# SCH_Mini-Converter_2024-05-02.net
KiCad netlist of a schematic drawn in EasyEDA
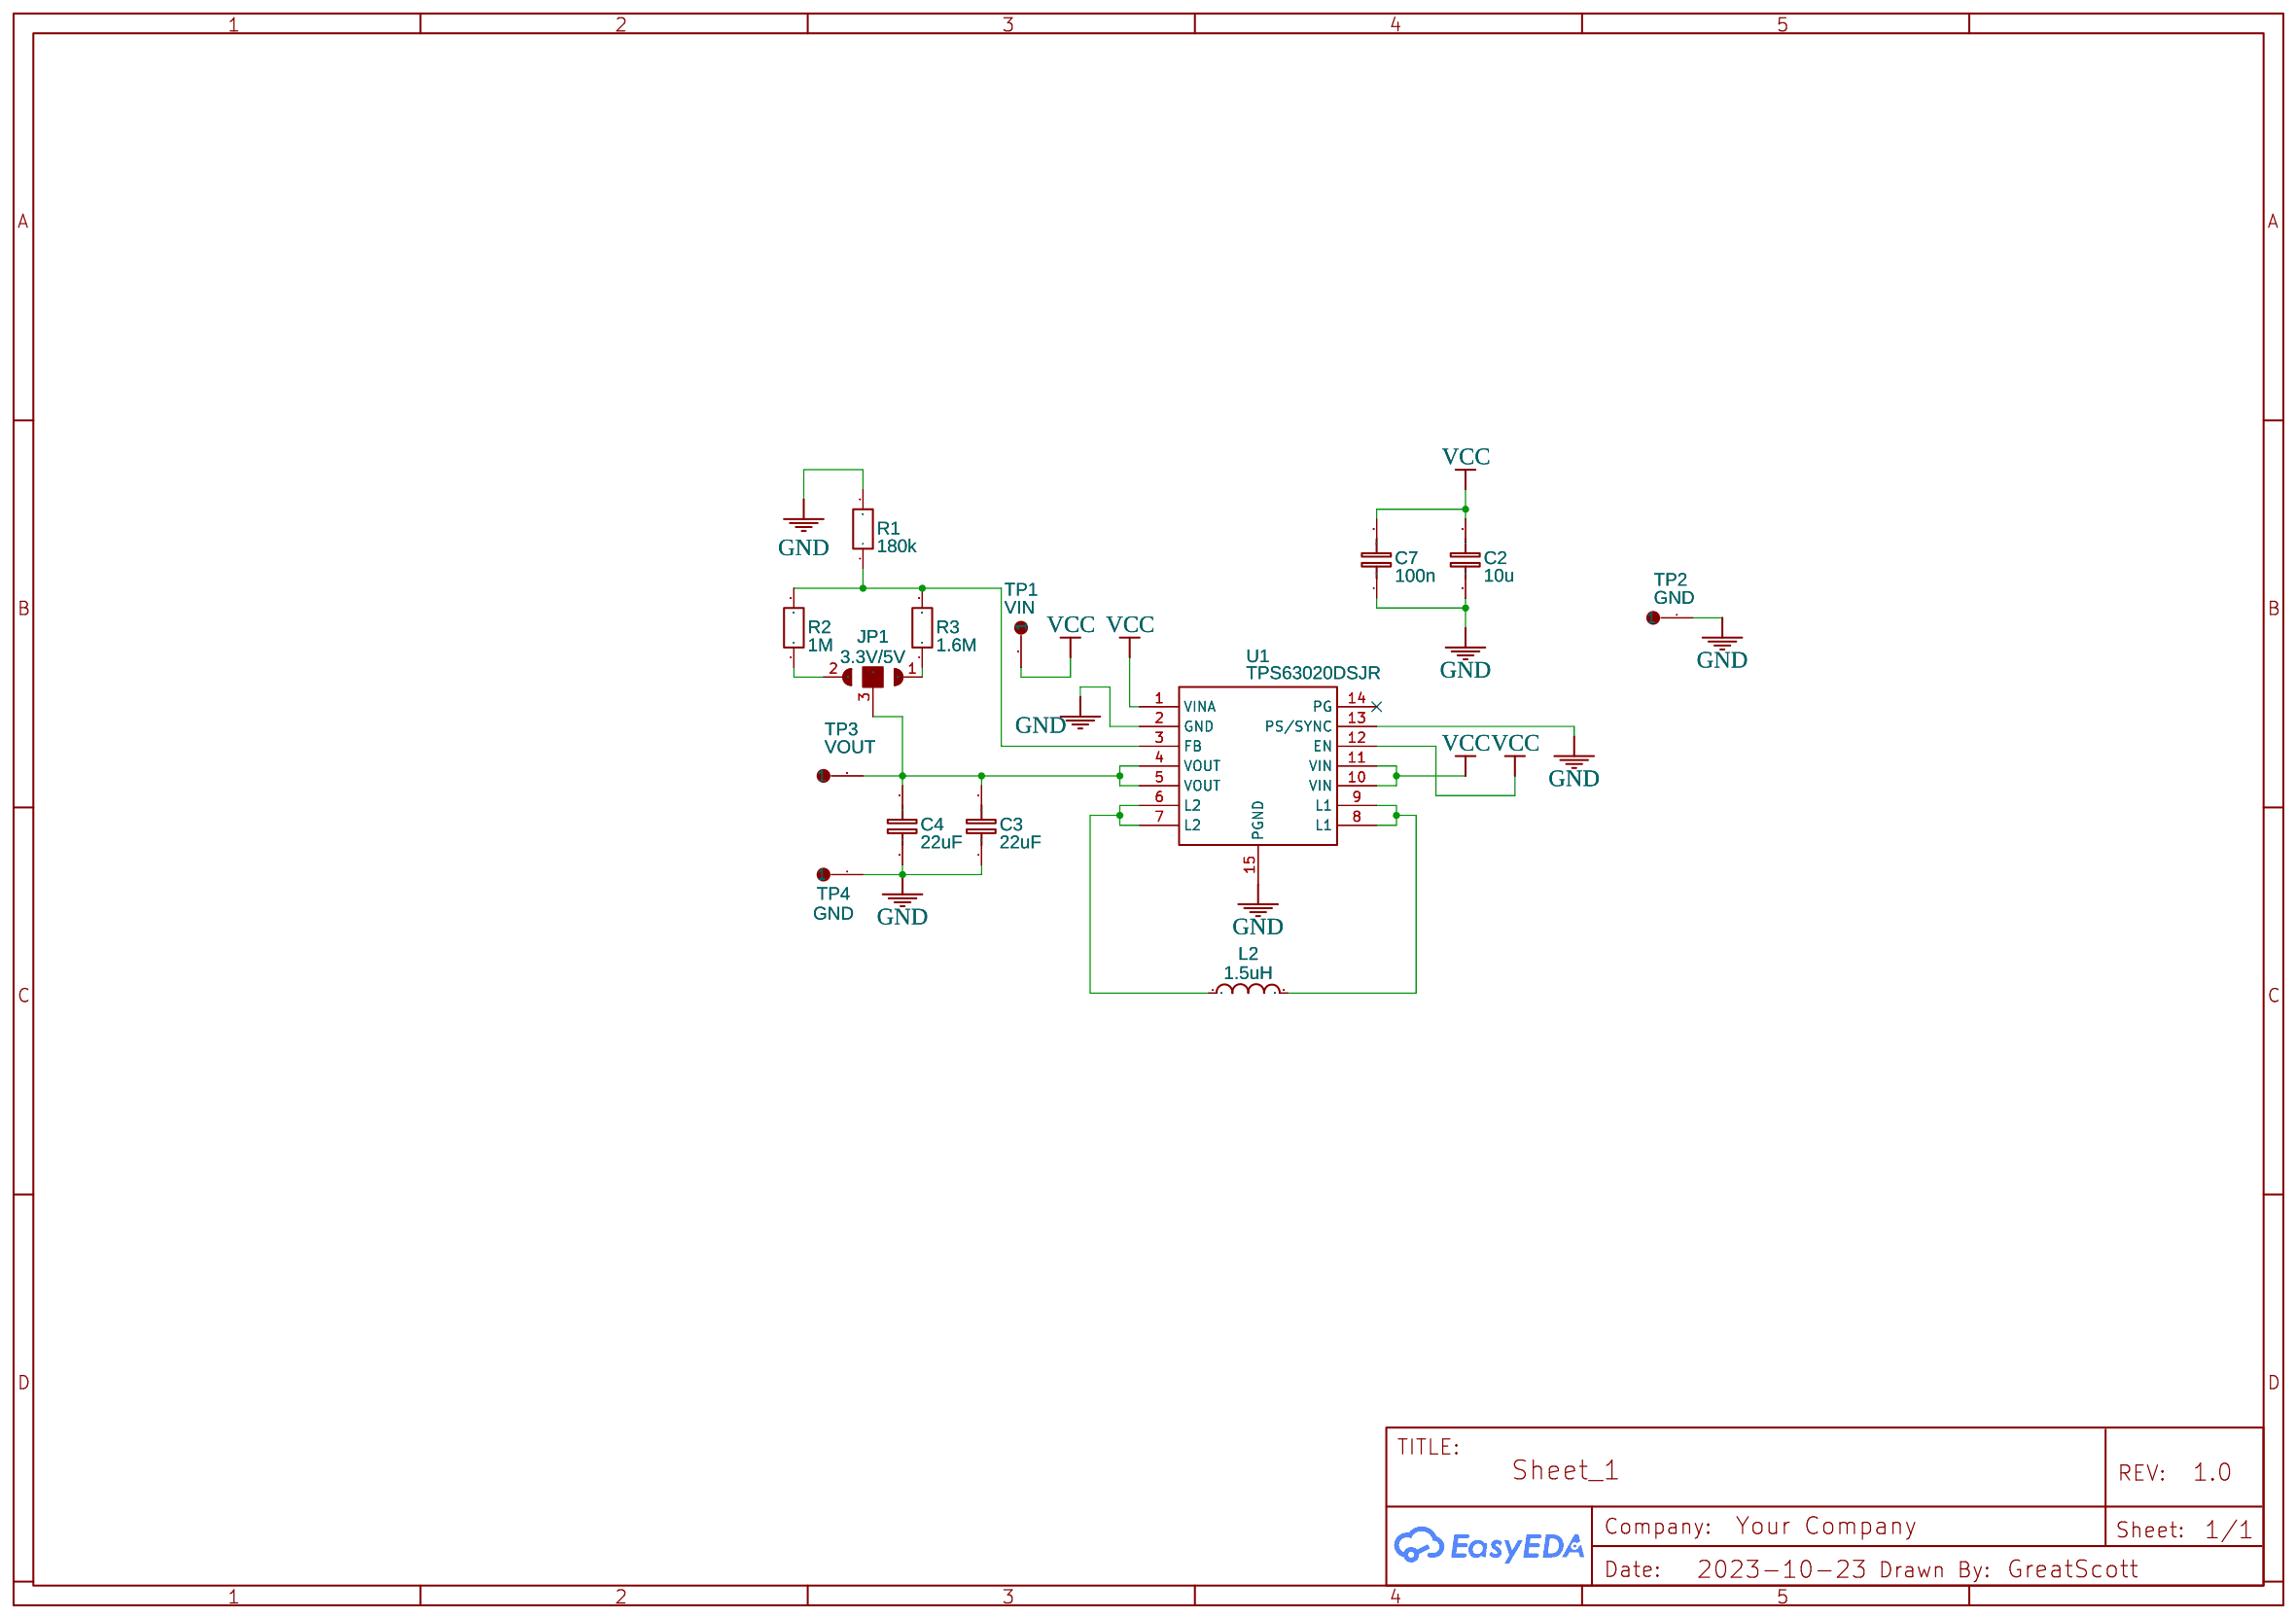
[diagram p0: schematic sheet]

(export (version "E")
  (design (tool "Eeschema 10.0.6"))
  (components
    (comp (ref "C2") (value "10u") (libsource (lib "") (part "C_0805_EU_1")))
    (comp (ref "C3") (value "22uF") (libsource (lib "") (part "C_0805_EU")))
    (comp (ref "C4") (value "22uF") (libsource (lib "") (part "C_0805_EU")))
    (comp (ref "C7") (value "100n") (libsource (lib "") (part "C_0805_EU_1")))
    (comp (ref "JP1") (value "3.3V/5V") (libsource (lib "") (part "SOLDER BRIDGE")))
    (comp (ref "L2")
      (value "1.5uH")
      (fields (field (name "Manufacturer Part") "78438336100"))
      (libsource (lib "") (part "78438336100"))
    )
    (comp (ref "R1") (value "180k") (libsource (lib "") (part "R_0805_EU")))
    (comp (ref "R2") (value "1M") (libsource (lib "") (part "R_0805_EU")))
    (comp (ref "R3") (value "1.6M") (libsource (lib "") (part "R_0805_EU")))
    (comp (ref "TP1") (value "VIN") (libsource (lib "") (part "TEST-POINT-PTH-1X1")))
    (comp (ref "TP2") (value "GND") (libsource (lib "") (part "TEST-POINT-PTH-1X1_1")))
    (comp (ref "TP3") (value "VOUT") (libsource (lib "") (part "TEST-POINT-PTH-1X1_1")))
    (comp (ref "TP4") (value "GND") (libsource (lib "") (part "TEST-POINT-PTH-1X1_1")))
    (comp (ref "U1")
      (value "TPS63020DSJR")
      (fields (field (name "Manufacturer") "TI(德州仪器)"))
      (libsource (lib "") (part "TPS63020DSJR"))
    )
  )
  (nets
    (net (code "1") (name "GND") (class "Default")
      (node (ref "C2") (pin "1") (pinfunction "1_1") (pintype "unspecified"))
      (node (ref "C3") (pin "1") (pinfunction "1_1") (pintype "unspecified"))
      (node (ref "C4") (pin "1") (pinfunction "1_1") (pintype "unspecified"))
      (node (ref "C7") (pin "1") (pinfunction "1_1") (pintype "unspecified"))
      (node (ref "R1") (pin "2") (pinfunction "2_2") (pintype "unspecified"))
      (node (ref "TP2") (pin "1") (pinfunction "1_1") (pintype "unspecified"))
      (node (ref "TP4") (pin "1") (pinfunction "1_1") (pintype "unspecified"))
      (node (ref "U1") (pin "13") (pinfunction "PS/SYNC_13") (pintype "unspecified"))
      (node (ref "U1") (pin "15") (pinfunction "PGND_15") (pintype "unspecified"))
      (node (ref "U1") (pin "2") (pinfunction "GND_2") (pintype "unspecified"))
    )
    (net (code "2") (name "Net-(C3-Pad2)") (class "Default")
      (node (ref "C3") (pin "2") (pinfunction "2_2") (pintype "unspecified"))
      (node (ref "C4") (pin "2") (pinfunction "2_2") (pintype "unspecified"))
      (node (ref "JP1") (pin "3") (pinfunction "3_3") (pintype "unspecified"))
      (node (ref "TP3") (pin "1") (pinfunction "1_1") (pintype "unspecified"))
      (node (ref "U1") (pin "4") (pinfunction "VOUT_4") (pintype "unspecified"))
      (node (ref "U1") (pin "5") (pinfunction "VOUT_5") (pintype "unspecified"))
    )
    (net (code "3") (name "Net-(JP1-Pad1)") (class "Default")
      (node (ref "JP1") (pin "1") (pinfunction "1_1") (pintype "unspecified"))
      (node (ref "R3") (pin "1") (pinfunction "1_1") (pintype "unspecified"))
    )
    (net (code "4") (name "Net-(JP1-Pad2)") (class "Default")
      (node (ref "JP1") (pin "2") (pinfunction "2_2") (pintype "unspecified"))
      (node (ref "R2") (pin "1") (pinfunction "1_1") (pintype "unspecified"))
    )
    (net (code "5") (name "Net-(L2-Pad1)") (class "Default")
      (node (ref "L2") (pin "1") (pinfunction "1_1") (pintype "unspecified"))
      (node (ref "U1") (pin "6") (pinfunction "L2_6") (pintype "unspecified"))
      (node (ref "U1") (pin "7") (pinfunction "L2_7") (pintype "unspecified"))
    )
    (net (code "6") (name "Net-(L2-Pad2)") (class "Default")
      (node (ref "L2") (pin "2") (pinfunction "2_2") (pintype "unspecified"))
      (node (ref "U1") (pin "8") (pinfunction "L1_8") (pintype "unspecified"))
      (node (ref "U1") (pin "9") (pinfunction "L1_9") (pintype "unspecified"))
    )
    (net (code "7") (name "Net-(U1-FB)") (class "Default")
      (node (ref "R1") (pin "1") (pinfunction "1_1") (pintype "unspecified"))
      (node (ref "R2") (pin "2") (pinfunction "2_2") (pintype "unspecified"))
      (node (ref "R3") (pin "2") (pinfunction "2_2") (pintype "unspecified"))
      (node (ref "U1") (pin "3") (pinfunction "FB_3") (pintype "unspecified"))
    )
    (net (code "8") (name "VCC") (class "Default")
      (node (ref "C2") (pin "2") (pinfunction "2_2") (pintype "unspecified"))
      (node (ref "C7") (pin "2") (pinfunction "2_2") (pintype "unspecified"))
      (node (ref "TP1") (pin "1") (pinfunction "1_1") (pintype "unspecified"))
      (node (ref "U1") (pin "1") (pinfunction "VINA_1") (pintype "unspecified"))
      (node (ref "U1") (pin "10") (pinfunction "VIN_10") (pintype "unspecified"))
      (node (ref "U1") (pin "11") (pinfunction "VIN_11") (pintype "unspecified"))
      (node (ref "U1") (pin "12") (pinfunction "EN_12") (pintype "unspecified"))
    )
    (net (code "9") (name "unconnected-(U1-PG-Pad14)") (class "Default")
      (node (ref "U1") (pin "14") (pinfunction "PG_14") (pintype "unspecified+no_connect"))
    )
  )
)
